# Bank_16_32_36.net
KiCad netlist of a schematic drawn in Altium Designer
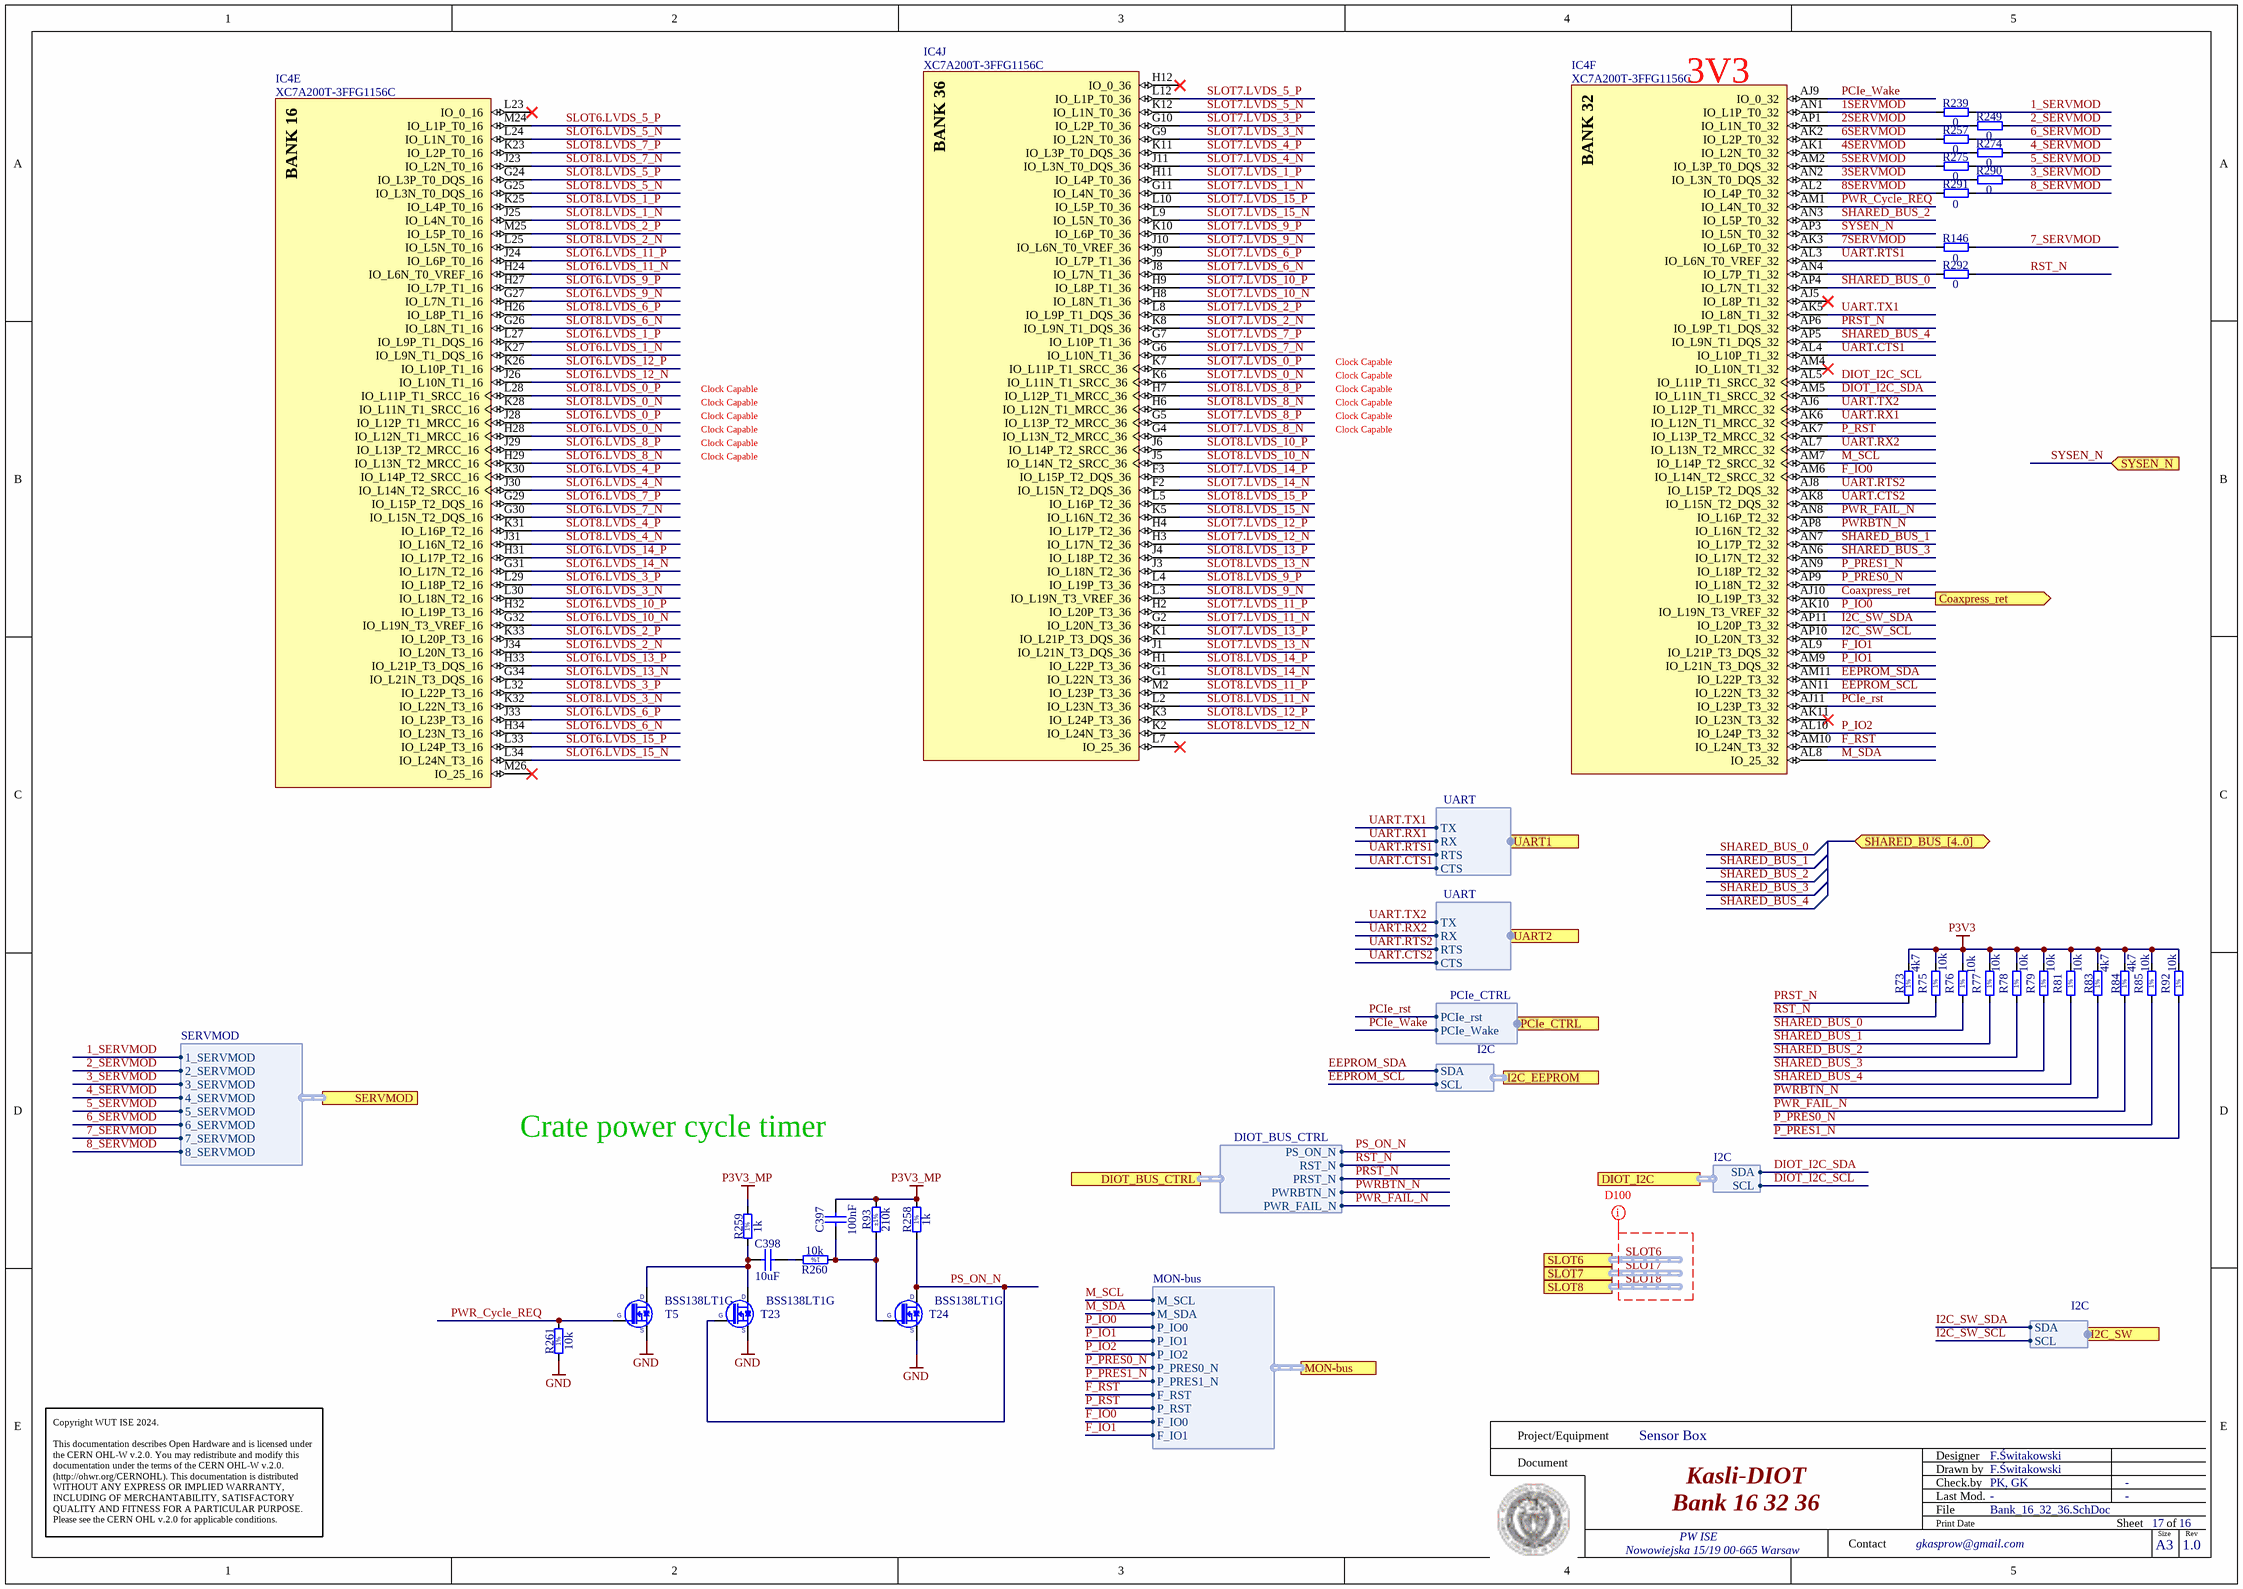
[diagram p0: Bank_16_32_36.SchDoc]

(export (version "E")
  (design (tool "Eeschema 10.0.6"))
  (components
    (comp (ref "C397")
      (value "100nF")
      (footprint "CAPC1005X55N")
      (description "Non-polarised capacitor")
      (fields
        (field (name "PART NUMBER") "CC0402_100NF_16V_10%_X7R")
        (field (name "VOLTAGE") "16V")
        (field (name "AUTHOR") "CERN DEM JLC")
      )
      (libsource (lib "Capacitors") (part "Capacitor - non polarized"))
    )
    (comp (ref "C398")
      (value "10uF")
      (footprint "CAPC3216X180N")
      (description "Non-polarised capacitor")
      (fields
        (field (name "PART NUMBER") "CC1206_10UF_25V_10%_X7R")
        (field (name "VOLTAGE") "25V")
        (field (name "AUTHOR") "CERN DEM JLC")
      )
      (libsource (lib "Capacitors") (part "Capacitor - non polarized"))
    )
    (comp (ref "IC4")
      (value "XC7A200T-3FFG1156C")
      (footprint "BGA1156C100P34X34_3500X3500X310")
      (description "Artix-7 FPGA, 500 User I/Os, 16 GTP, 1156-Ball BGA, , Speed Grade 3, Commercial Grade, Pb-Free")
      (fields (field (name "MANUFACTURER") "XILINX") (field (name "AUTHOR") "CERN DEM JLC"))
      (libsource (lib "ICs And Semiconductors") (part "XC7A200T-3FFG1156C"))
    )
    (comp (ref "R73")
      (value "4k7")
      (footprint "RESC1005X40N")
      (description "Resistor - 1%")
      (fields
        (field (name "PART NUMBER") "R0402_4K7_1%_0.0625W_100PPM")
        (field (name "POWER") "0.0625W")
        (field (name "AUTHOR") "CERN DEM JLC")
      )
      (libsource (lib "Resistors") (part "Resistor - 1%"))
    )
    (comp (ref "R75")
      (value "10k")
      (footprint "RESC1005X40N")
      (description "Resistor - 1%")
      (fields
        (field (name "PART NUMBER") "R0402_10K_1%_0.0625W_100PPM")
        (field (name "POWER") "0.0625W")
        (field (name "AUTHOR") "CERN DEM JLC")
      )
      (libsource (lib "Resistors") (part "Resistor - 1%"))
    )
    (comp (ref "R76")
      (value "10k")
      (footprint "RESC1005X40N")
      (description "Resistor - 1%")
      (fields
        (field (name "PART NUMBER") "R0402_10K_1%_0.0625W_100PPM")
        (field (name "POWER") "0.0625W")
        (field (name "AUTHOR") "CERN DEM JLC")
      )
      (libsource (lib "Resistors") (part "Resistor - 1%"))
    )
    (comp (ref "R77")
      (value "10k")
      (footprint "RESC1005X40N")
      (description "Resistor - 1%")
      (fields
        (field (name "PART NUMBER") "R0402_10K_1%_0.0625W_100PPM")
        (field (name "POWER") "0.0625W")
        (field (name "AUTHOR") "CERN DEM JLC")
      )
      (libsource (lib "Resistors") (part "Resistor - 1%"))
    )
    (comp (ref "R78")
      (value "10k")
      (footprint "RESC1005X40N")
      (description "Resistor - 1%")
      (fields
        (field (name "PART NUMBER") "R0402_10K_1%_0.0625W_100PPM")
        (field (name "POWER") "0.0625W")
        (field (name "AUTHOR") "CERN DEM JLC")
      )
      (libsource (lib "Resistors") (part "Resistor - 1%"))
    )
    (comp (ref "R79")
      (value "10k")
      (footprint "RESC1005X40N")
      (description "Resistor - 1%")
      (fields
        (field (name "PART NUMBER") "R0402_10K_1%_0.0625W_100PPM")
        (field (name "POWER") "0.0625W")
        (field (name "AUTHOR") "CERN DEM JLC")
      )
      (libsource (lib "Resistors") (part "Resistor - 1%"))
    )
    (comp (ref "R81")
      (value "10k")
      (footprint "RESC1005X40N")
      (description "Resistor - 1%")
      (fields
        (field (name "PART NUMBER") "R0402_10K_1%_0.0625W_100PPM")
        (field (name "POWER") "0.0625W")
        (field (name "AUTHOR") "CERN DEM JLC")
      )
      (libsource (lib "Resistors") (part "Resistor - 1%"))
    )
    (comp (ref "R83")
      (value "4k7")
      (footprint "RESC1005X40N")
      (description "Resistor - 1%")
      (fields
        (field (name "PART NUMBER") "R0402_4K7_1%_0.0625W_100PPM")
        (field (name "POWER") "0.0625W")
        (field (name "AUTHOR") "CERN DEM JLC")
      )
      (libsource (lib "Resistors") (part "Resistor - 1%"))
    )
    (comp (ref "R84")
      (value "4k7")
      (footprint "RESC1005X40N")
      (description "Resistor - 1%")
      (fields
        (field (name "PART NUMBER") "R0402_4K7_1%_0.0625W_100PPM")
        (field (name "POWER") "0.0625W")
        (field (name "AUTHOR") "CERN DEM JLC")
      )
      (libsource (lib "Resistors") (part "Resistor - 1%"))
    )
    (comp (ref "R85")
      (value "10k")
      (footprint "RESC1005X40N")
      (description "Resistor - 1%")
      (fields
        (field (name "PART NUMBER") "R0402_10K_1%_0.0625W_100PPM")
        (field (name "POWER") "0.0625W")
        (field (name "AUTHOR") "CERN DEM JLC")
      )
      (libsource (lib "Resistors") (part "Resistor - 1%"))
    )
    (comp (ref "R92")
      (value "10k")
      (footprint "RESC1005X40N")
      (description "Resistor - 1%")
      (fields
        (field (name "PART NUMBER") "R0402_10K_1%_0.0625W_100PPM")
        (field (name "POWER") "0.0625W")
        (field (name "AUTHOR") "CERN DEM JLC")
      )
      (libsource (lib "Resistors") (part "Resistor - 1%"))
    )
    (comp (ref "R93")
      (value "210k")
      (footprint "RESC1005X40N")
      (description "Resistor - 1%")
      (fields
        (field (name "TOLERANCE") "±1%")
        (field (name "PART NUMBER") "R0402_210K_1%_0.063W_100PPM")
        (field (name "POWER") "0.063W")
        (field (name "AUTHOR") "CERN DEM BC")
      )
      (libsource (lib "Resistors") (part "Resistor - 1%"))
    )
    (comp (ref "R146")
      (value "0")
      (footprint "RESC1005X40N")
      (description "Resistor")
      (fields
        (field (name "PART NUMBER") "R0402_0R_JUMPER")
        (field (name "MANUFACTURER") "GENERIC")
        (field (name "AUTHOR") "CERN DEM JLC")
      )
      (libsource (lib "Resistors") (part "Resistor"))
    )
    (comp (ref "R239")
      (value "0")
      (footprint "RESC1005X40N")
      (description "Resistor")
      (fields
        (field (name "PART NUMBER") "R0402_0R_JUMPER")
        (field (name "MANUFACTURER") "GENERIC")
        (field (name "AUTHOR") "CERN DEM JLC")
      )
      (libsource (lib "Resistors") (part "Resistor"))
    )
    (comp (ref "R249")
      (value "0")
      (footprint "RESC1005X40N")
      (description "Resistor")
      (fields
        (field (name "PART NUMBER") "R0402_0R_JUMPER")
        (field (name "MANUFACTURER") "GENERIC")
        (field (name "AUTHOR") "CERN DEM JLC")
      )
      (libsource (lib "Resistors") (part "Resistor"))
    )
    (comp (ref "R257")
      (value "0")
      (footprint "RESC1005X40N")
      (description "Resistor")
      (fields
        (field (name "PART NUMBER") "R0402_0R_JUMPER")
        (field (name "MANUFACTURER") "GENERIC")
        (field (name "AUTHOR") "CERN DEM JLC")
      )
      (libsource (lib "Resistors") (part "Resistor"))
    )
    (comp (ref "R258")
      (value "1k")
      (footprint "RESC1005X40N")
      (description "Resistor - 1%")
      (fields
        (field (name "PART NUMBER") "R0402_1K_1%_0.0625W_100PPM")
        (field (name "POWER") "0.0625W")
        (field (name "AUTHOR") "CERN DEM JLC")
      )
      (libsource (lib "Resistors") (part "Resistor - 1%"))
    )
    (comp (ref "R259")
      (value "1k")
      (footprint "RESC1005X40N")
      (description "Resistor - 1%")
      (fields
        (field (name "PART NUMBER") "R0402_1K_1%_0.0625W_100PPM")
        (field (name "POWER") "0.0625W")
        (field (name "AUTHOR") "CERN DEM JLC")
      )
      (libsource (lib "Resistors") (part "Resistor - 1%"))
    )
    (comp (ref "R260")
      (value "10k")
      (footprint "RESC1005X40N")
      (description "Resistor - 1%")
      (fields
        (field (name "PART NUMBER") "R0402_10K_1%_0.0625W_100PPM")
        (field (name "POWER") "0.0625W")
        (field (name "AUTHOR") "CERN DEM JLC")
      )
      (libsource (lib "Resistors") (part "Resistor - 1%"))
    )
    (comp (ref "R261")
      (value "10k")
      (footprint "RESC1005X40N")
      (description "Resistor - 1%")
      (fields
        (field (name "PART NUMBER") "R0402_10K_1%_0.0625W_100PPM")
        (field (name "POWER") "0.0625W")
        (field (name "AUTHOR") "CERN DEM JLC")
      )
      (libsource (lib "Resistors") (part "Resistor - 1%"))
    )
    (comp (ref "R274")
      (value "0")
      (footprint "RESC1005X40N")
      (description "Resistor")
      (fields
        (field (name "PART NUMBER") "R0402_0R_JUMPER")
        (field (name "MANUFACTURER") "GENERIC")
        (field (name "AUTHOR") "CERN DEM JLC")
      )
      (libsource (lib "Resistors") (part "Resistor"))
    )
    (comp (ref "R275")
      (value "0")
      (footprint "RESC1005X40N")
      (description "Resistor")
      (fields
        (field (name "PART NUMBER") "R0402_0R_JUMPER")
        (field (name "MANUFACTURER") "GENERIC")
        (field (name "AUTHOR") "CERN DEM JLC")
      )
      (libsource (lib "Resistors") (part "Resistor"))
    )
    (comp (ref "R290")
      (value "0")
      (footprint "RESC1005X40N")
      (description "Resistor")
      (fields
        (field (name "PART NUMBER") "R0402_0R_JUMPER")
        (field (name "MANUFACTURER") "GENERIC")
        (field (name "AUTHOR") "CERN DEM JLC")
      )
      (libsource (lib "Resistors") (part "Resistor"))
    )
    (comp (ref "R291")
      (value "0")
      (footprint "RESC1005X40N")
      (description "Resistor")
      (fields
        (field (name "PART NUMBER") "R0402_0R_JUMPER")
        (field (name "MANUFACTURER") "GENERIC")
        (field (name "AUTHOR") "CERN DEM JLC")
      )
      (libsource (lib "Resistors") (part "Resistor"))
    )
    (comp (ref "R292")
      (value "0")
      (footprint "RESC1005X40N")
      (description "Resistor")
      (fields
        (field (name "PART NUMBER") "R0402_0R_JUMPER")
        (field (name "MANUFACTURER") "GENERIC")
        (field (name "AUTHOR") "CERN DEM JLC")
      )
      (libsource (lib "Resistors") (part "Resistor"))
    )
    (comp (ref "T5")
      (value "BSS138LT1G")
      (footprint "SOT95P240X110-3N")
      (description "N-CHANNEL MOSFET WITH DIODE")
      (fields
        (field (name "MANUFACTURER") "ON SEMICONDUCTOR")
        (field (name "MANUFACTURER PART NUMBER") "BSS138L")
        (field (name "AUTHOR") "CERN DEM JLC")
      )
      (libsource (lib "ICs And Semiconductors") (part "N-MOSFET-D 1G 2S 3D"))
    )
    (comp (ref "T23")
      (value "BSS138LT1G")
      (footprint "SOT95P240X110-3N")
      (description "N-CHANNEL MOSFET WITH DIODE")
      (fields
        (field (name "MANUFACTURER") "ON SEMICONDUCTOR")
        (field (name "MANUFACTURER PART NUMBER") "BSS138L")
        (field (name "AUTHOR") "CERN DEM JLC")
      )
      (libsource (lib "ICs And Semiconductors") (part "N-MOSFET-D 1G 2S 3D"))
    )
    (comp (ref "T24")
      (value "BSS138LT1G")
      (footprint "SOT95P240X110-3N")
      (description "N-CHANNEL MOSFET WITH DIODE")
      (fields
        (field (name "MANUFACTURER") "ON SEMICONDUCTOR")
        (field (name "MANUFACTURER PART NUMBER") "BSS138L")
        (field (name "AUTHOR") "CERN DEM JLC")
      )
      (libsource (lib "ICs And Semiconductors") (part "N-MOSFET-D 1G 2S 3D"))
    )
  )
  (nets
    (net (code "10") (name "/1SERVMOD") (class "Default")
      (node (ref "IC4") (pin "AN1") (pinfunction "IO_L1P_T0_32_AN1") (pintype "bidirectional"))
      (node (ref "R239") (pin "1") (pinfunction "1_1") (pintype "passive"))
    )
    (net (code "11") (name "/1_SERVMOD") (class "Default")
      (node (ref "R239") (pin "2") (pinfunction "2_2") (pintype "passive"))
    )
    (net (code "12") (name "/2SERVMOD") (class "Default")
      (node (ref "IC4") (pin "AP1") (pinfunction "IO_L1N_T0_32_AP1") (pintype "bidirectional"))
      (node (ref "R249") (pin "1") (pinfunction "1_1") (pintype "passive"))
    )
    (net (code "13") (name "/2_SERVMOD") (class "Default")
      (node (ref "R249") (pin "2") (pinfunction "2_2") (pintype "passive"))
    )
    (net (code "14") (name "/3SERVMOD") (class "Default")
      (node (ref "IC4") (pin "AN2") (pinfunction "IO_L3N_T0_DQS_32_AN2") (pintype "bidirectional"))
      (node (ref "R290") (pin "1") (pinfunction "1_1") (pintype "passive"))
    )
    (net (code "15") (name "/3_SERVMOD") (class "Default")
      (node (ref "R290") (pin "2") (pinfunction "2_2") (pintype "passive"))
    )
    (net (code "16") (name "/4SERVMOD") (class "Default")
      (node (ref "IC4") (pin "AK1") (pinfunction "IO_L2N_T0_32_AK1") (pintype "bidirectional"))
      (node (ref "R274") (pin "1") (pinfunction "1_1") (pintype "passive"))
    )
    (net (code "17") (name "/4_SERVMOD") (class "Default")
      (node (ref "R274") (pin "2") (pinfunction "2_2") (pintype "passive"))
    )
    (net (code "18") (name "/5SERVMOD") (class "Default")
      (node (ref "IC4") (pin "AM2") (pinfunction "IO_L3P_T0_DQS_32_AM2") (pintype "bidirectional"))
      (node (ref "R275") (pin "1") (pinfunction "1_1") (pintype "passive"))
    )
    (net (code "19") (name "/5_SERVMOD") (class "Default")
      (node (ref "R275") (pin "2") (pinfunction "2_2") (pintype "passive"))
    )
    (net (code "20") (name "/6SERVMOD") (class "Default")
      (node (ref "IC4") (pin "AK2") (pinfunction "IO_L2P_T0_32_AK2") (pintype "bidirectional"))
      (node (ref "R257") (pin "1") (pinfunction "1_1") (pintype "passive"))
    )
    (net (code "21") (name "/6_SERVMOD") (class "Default")
      (node (ref "R257") (pin "2") (pinfunction "2_2") (pintype "passive"))
    )
    (net (code "22") (name "/7SERVMOD") (class "Default")
      (node (ref "IC4") (pin "AK3") (pinfunction "IO_L6P_T0_32_AK3") (pintype "bidirectional"))
      (node (ref "R146") (pin "1") (pinfunction "1_1") (pintype "passive"))
    )
    (net (code "23") (name "/7_SERVMOD") (class "Default")
      (node (ref "R146") (pin "2") (pinfunction "2_2") (pintype "passive"))
    )
    (net (code "24") (name "/8SERVMOD") (class "Default")
      (node (ref "IC4") (pin "AL2") (pinfunction "IO_L4P_T0_32_AL2") (pintype "bidirectional"))
      (node (ref "R291") (pin "1") (pinfunction "1_1") (pintype "passive"))
    )
    (net (code "25") (name "/8_SERVMOD") (class "Default")
      (node (ref "R291") (pin "2") (pinfunction "2_2") (pintype "passive"))
    )
    (net (code "26") (name "/Coaxpress_ret") (class "Default")
      (node (ref "IC4") (pin "AJ10") (pinfunction "IO_L19P_T3_32_AJ10") (pintype "bidirectional"))
    )
    (net (code "27") (name "/DIOT_I2C_SCL") (class "Default")
      (node (ref "IC4") (pin "AL5") (pinfunction "IO_L11P_T1_SRCC_32_AL5") (pintype "bidirectional"))
    )
    (net (code "28") (name "/DIOT_I2C_SDA") (class "Default")
      (node (ref "IC4") (pin "AM5") (pinfunction "IO_L11N_T1_SRCC_32_AM5") (pintype "bidirectional"))
    )
    (net (code "29") (name "/EEPROM_SCL") (class "Default")
      (node (ref "IC4") (pin "AN11") (pinfunction "IO_L22N_T3_32_AN11") (pintype "bidirectional"))
    )
    (net (code "30") (name "/EEPROM_SDA") (class "Default")
      (node (ref "IC4") (pin "AM11") (pinfunction "IO_L22P_T3_32_AM11") (pintype "bidirectional"))
    )
    (net (code "31") (name "/F_IO0") (class "Default")
      (node (ref "IC4") (pin "AM6") (pinfunction "IO_L14N_T2_SRCC_32_AM6") (pintype "bidirectional"))
    )
    (net (code "32") (name "/F_IO1") (class "Default")
      (node (ref "IC4") (pin "AL9") (pinfunction "IO_L21P_T3_DQS_32_AL9") (pintype "bidirectional"))
    )
    (net (code "33") (name "/F_RST") (class "Default")
      (node (ref "IC4") (pin "AM10") (pinfunction "IO_L24N_T3_32_AM10") (pintype "bidirectional"))
    )
    (net (code "34") (name "/I2C_SW_SCL") (class "Default")
      (node (ref "IC4") (pin "AP10") (pinfunction "IO_L20N_T3_32_AP10") (pintype "bidirectional"))
    )
    (net (code "35") (name "/I2C_SW_SDA") (class "Default")
      (node (ref "IC4") (pin "AP11") (pinfunction "IO_L20P_T3_32_AP11") (pintype "bidirectional"))
    )
    (net (code "36") (name "/M_SCL") (class "Default")
      (node (ref "IC4") (pin "AM7") (pinfunction "IO_L14P_T2_SRCC_32_AM7") (pintype "bidirectional"))
    )
    (net (code "37") (name "/M_SDA") (class "Default")
      (node (ref "IC4") (pin "AL8") (pinfunction "IO_25_32_AL8") (pintype "bidirectional"))
    )
    (net (code "38") (name "/PCIe_Wake") (class "Default")
      (node (ref "IC4") (pin "AJ9") (pinfunction "IO_0_32_AJ9") (pintype "bidirectional"))
    )
    (net (code "39") (name "/PCIe_rst") (class "Default")
      (node (ref "IC4") (pin "AJ11") (pinfunction "IO_L23P_T3_32_AJ11") (pintype "bidirectional"))
    )
    (net (code "40") (name "/PRST_N") (class "Default")
      (node (ref "IC4") (pin "AP6") (pinfunction "IO_L9P_T1_DQS_32_AP6") (pintype "bidirectional"))
      (node (ref "R73") (pin "1") (pinfunction "1_1") (pintype "passive"))
    )
    (net (code "41") (name "/PS_ON_N") (class "Default")
      (node (ref "R258") (pin "1") (pinfunction "1_1") (pintype "passive"))
      (node (ref "T23") (pin "1") (pinfunction "G_1") (pintype "passive"))
      (node (ref "T24") (pin "3") (pinfunction "D_3") (pintype "passive"))
    )
    (net (code "42") (name "/PWRBTN_N") (class "Default")
      (node (ref "IC4") (pin "AP8") (pinfunction "IO_L16N_T2_32_AP8") (pintype "bidirectional"))
      (node (ref "R83") (pin "1") (pinfunction "1_1") (pintype "passive"))
    )
    (net (code "43") (name "/PWR_Cycle_REQ") (class "Default")
      (node (ref "IC4") (pin "AM1") (pinfunction "IO_L4N_T0_32_AM1") (pintype "bidirectional"))
      (node (ref "R261") (pin "2") (pinfunction "2_2") (pintype "passive"))
      (node (ref "T5") (pin "1") (pinfunction "G_1") (pintype "passive"))
    )
    (net (code "44") (name "/PWR_FAIL_N") (class "Default")
      (node (ref "IC4") (pin "AN8") (pinfunction "IO_L16P_T2_32_AN8") (pintype "bidirectional"))
      (node (ref "R84") (pin "1") (pinfunction "1_1") (pintype "passive"))
    )
    (net (code "45") (name "/P_IO0") (class "Default")
      (node (ref "IC4") (pin "AK10") (pinfunction "IO_L19N_T3_VREF_32_AK10") (pintype "bidirectional"))
    )
    (net (code "46") (name "/P_IO1") (class "Default")
      (node (ref "IC4") (pin "AM9") (pinfunction "IO_L21N_T3_DQS_32_AM9") (pintype "bidirectional"))
    )
    (net (code "47") (name "/P_IO2") (class "Default")
      (node (ref "IC4") (pin "AL10") (pinfunction "IO_L24P_T3_32_AL10") (pintype "bidirectional"))
    )
    (net (code "48") (name "/P_PRES0_N") (class "Default")
      (node (ref "IC4") (pin "AP9") (pinfunction "IO_L18N_T2_32_AP9") (pintype "bidirectional"))
      (node (ref "R85") (pin "1") (pinfunction "1_1") (pintype "passive"))
    )
    (net (code "49") (name "/P_PRES1_N") (class "Default")
      (node (ref "IC4") (pin "AN9") (pinfunction "IO_L18P_T2_32_AN9") (pintype "bidirectional"))
      (node (ref "R92") (pin "1") (pinfunction "1_1") (pintype "passive"))
    )
    (net (code "50") (name "/P_RST") (class "Default")
      (node (ref "IC4") (pin "AK7") (pinfunction "IO_L13P_T2_MRCC_32_AK7") (pintype "bidirectional"))
    )
    (net (code "51") (name "/RST_N") (class "Default")
      (node (ref "R292") (pin "2") (pinfunction "2_2") (pintype "passive"))
      (node (ref "R75") (pin "1") (pinfunction "1_1") (pintype "passive"))
    )
    (net (code "52") (name "/SHARED_BUS_0") (class "Default")
      (node (ref "IC4") (pin "AP4") (pinfunction "IO_L7N_T1_32_AP4") (pintype "bidirectional"))
      (node (ref "R76") (pin "1") (pinfunction "1_1") (pintype "passive"))
    )
    (net (code "53") (name "/SHARED_BUS_1") (class "Default")
      (node (ref "IC4") (pin "AN7") (pinfunction "IO_L17P_T2_32_AN7") (pintype "bidirectional"))
      (node (ref "R77") (pin "1") (pinfunction "1_1") (pintype "passive"))
    )
    (net (code "54") (name "/SHARED_BUS_2") (class "Default")
      (node (ref "IC4") (pin "AN3") (pinfunction "IO_L5P_T0_32_AN3") (pintype "bidirectional"))
      (node (ref "R78") (pin "1") (pinfunction "1_1") (pintype "passive"))
    )
    (net (code "55") (name "/SHARED_BUS_3") (class "Default")
      (node (ref "IC4") (pin "AN6") (pinfunction "IO_L17N_T2_32_AN6") (pintype "bidirectional"))
      (node (ref "R79") (pin "1") (pinfunction "1_1") (pintype "passive"))
    )
    (net (code "56") (name "/SHARED_BUS_4") (class "Default")
      (node (ref "IC4") (pin "AP5") (pinfunction "IO_L9N_T1_DQS_32_AP5") (pintype "bidirectional"))
      (node (ref "R81") (pin "1") (pinfunction "1_1") (pintype "passive"))
    )
    (net (code "58") (name "/SLOT6.LVDS_0_N") (class "Default")
      (node (ref "IC4") (pin "H28") (pinfunction "IO_L12N_T1_MRCC_16_H28") (pintype "bidirectional"))
    )
    (net (code "59") (name "/SLOT6.LVDS_0_P") (class "Default")
      (node (ref "IC4") (pin "J28") (pinfunction "IO_L12P_T1_MRCC_16_J28") (pintype "bidirectional"))
    )
    (net (code "60") (name "/SLOT6.LVDS_1_N") (class "Default")
      (node (ref "IC4") (pin "K27") (pinfunction "IO_L9N_T1_DQS_16_K27") (pintype "bidirectional"))
    )
    (net (code "61") (name "/SLOT6.LVDS_1_P") (class "Default")
      (node (ref "IC4") (pin "L27") (pinfunction "IO_L9P_T1_DQS_16_L27") (pintype "bidirectional"))
    )
    (net (code "62") (name "/SLOT6.LVDS_2_N") (class "Default")
      (node (ref "IC4") (pin "J34") (pinfunction "IO_L20N_T3_16_J34") (pintype "bidirectional"))
    )
    (net (code "63") (name "/SLOT6.LVDS_2_P") (class "Default")
      (node (ref "IC4") (pin "K33") (pinfunction "IO_L20P_T3_16_K33") (pintype "bidirectional"))
    )
    (net (code "64") (name "/SLOT6.LVDS_3_N") (class "Default")
      (node (ref "IC4") (pin "L30") (pinfunction "IO_L18N_T2_16_L30") (pintype "bidirectional"))
    )
    (net (code "65") (name "/SLOT6.LVDS_3_P") (class "Default")
      (node (ref "IC4") (pin "L29") (pinfunction "IO_L18P_T2_16_L29") (pintype "bidirectional"))
    )
    (net (code "66") (name "/SLOT6.LVDS_4_N") (class "Default")
      (node (ref "IC4") (pin "J30") (pinfunction "IO_L14N_T2_SRCC_16_J30") (pintype "bidirectional"))
    )
    (net (code "67") (name "/SLOT6.LVDS_4_P") (class "Default")
      (node (ref "IC4") (pin "K30") (pinfunction "IO_L14P_T2_SRCC_16_K30") (pintype "bidirectional"))
    )
    (net (code "68") (name "/SLOT6.LVDS_5_N") (class "Default")
      (node (ref "IC4") (pin "L24") (pinfunction "IO_L1N_T0_16_L24") (pintype "bidirectional"))
    )
    (net (code "69") (name "/SLOT6.LVDS_5_P") (class "Default")
      (node (ref "IC4") (pin "M24") (pinfunction "IO_L1P_T0_16_M24") (pintype "bidirectional"))
    )
    (net (code "70") (name "/SLOT6.LVDS_6_N") (class "Default")
      (node (ref "IC4") (pin "H34") (pinfunction "IO_L23N_T3_16_H34") (pintype "bidirectional"))
    )
    (net (code "71") (name "/SLOT6.LVDS_6_P") (class "Default")
      (node (ref "IC4") (pin "J33") (pinfunction "IO_L23P_T3_16_J33") (pintype "bidirectional"))
    )
    (net (code "72") (name "/SLOT6.LVDS_7_N") (class "Default")
      (node (ref "IC4") (pin "G30") (pinfunction "IO_L15N_T2_DQS_16_G30") (pintype "bidirectional"))
    )
    (net (code "73") (name "/SLOT6.LVDS_7_P") (class "Default")
      (node (ref "IC4") (pin "G29") (pinfunction "IO_L15P_T2_DQS_16_G29") (pintype "bidirectional"))
    )
    (net (code "74") (name "/SLOT6.LVDS_8_N") (class "Default")
      (node (ref "IC4") (pin "H29") (pinfunction "IO_L13N_T2_MRCC_16_H29") (pintype "bidirectional"))
    )
    (net (code "75") (name "/SLOT6.LVDS_8_P") (class "Default")
      (node (ref "IC4") (pin "J29") (pinfunction "IO_L13P_T2_MRCC_16_J29") (pintype "bidirectional"))
    )
    (net (code "76") (name "/SLOT6.LVDS_9_N") (class "Default")
      (node (ref "IC4") (pin "G27") (pinfunction "IO_L7N_T1_16_G27") (pintype "bidirectional"))
    )
    (net (code "77") (name "/SLOT6.LVDS_9_P") (class "Default")
      (node (ref "IC4") (pin "H27") (pinfunction "IO_L7P_T1_16_H27") (pintype "bidirectional"))
    )
    (net (code "78") (name "/SLOT6.LVDS_10_N") (class "Default")
      (node (ref "IC4") (pin "G32") (pinfunction "IO_L19N_T3_VREF_16_G32") (pintype "bidirectional"))
    )
    (net (code "79") (name "/SLOT6.LVDS_10_P") (class "Default")
      (node (ref "IC4") (pin "H32") (pinfunction "IO_L19P_T3_16_H32") (pintype "bidirectional"))
    )
    (net (code "80") (name "/SLOT6.LVDS_11_N") (class "Default")
      (node (ref "IC4") (pin "H24") (pinfunction "IO_L6N_T0_VREF_16_H24") (pintype "bidirectional"))
    )
    (net (code "81") (name "/SLOT6.LVDS_11_P") (class "Default")
      (node (ref "IC4") (pin "J24") (pinfunction "IO_L6P_T0_16_J24") (pintype "bidirectional"))
    )
    (net (code "82") (name "/SLOT6.LVDS_12_N") (class "Default")
      (node (ref "IC4") (pin "J26") (pinfunction "IO_L10N_T1_16_J26") (pintype "bidirectional"))
    )
    (net (code "83") (name "/SLOT6.LVDS_12_P") (class "Default")
      (node (ref "IC4") (pin "K26") (pinfunction "IO_L10P_T1_16_K26") (pintype "bidirectional"))
    )
    (net (code "84") (name "/SLOT6.LVDS_13_N") (class "Default")
      (node (ref "IC4") (pin "G34") (pinfunction "IO_L21N_T3_DQS_16_G34") (pintype "bidirectional"))
    )
    (net (code "85") (name "/SLOT6.LVDS_13_P") (class "Default")
      (node (ref "IC4") (pin "H33") (pinfunction "IO_L21P_T3_DQS_16_H33") (pintype "bidirectional"))
    )
    (net (code "86") (name "/SLOT6.LVDS_14_N") (class "Default")
      (node (ref "IC4") (pin "G31") (pinfunction "IO_L17N_T2_16_G31") (pintype "bidirectional"))
    )
    (net (code "87") (name "/SLOT6.LVDS_14_P") (class "Default")
      (node (ref "IC4") (pin "H31") (pinfunction "IO_L17P_T2_16_H31") (pintype "bidirectional"))
    )
    (net (code "88") (name "/SLOT6.LVDS_15_N") (class "Default")
      (node (ref "IC4") (pin "L34") (pinfunction "IO_L24N_T3_16_L34") (pintype "bidirectional"))
    )
    (net (code "89") (name "/SLOT6.LVDS_15_P") (class "Default")
      (node (ref "IC4") (pin "L33") (pinfunction "IO_L24P_T3_16_L33") (pintype "bidirectional"))
    )
    (net (code "90") (name "/SLOT7.LVDS_0_N") (class "Default")
      (node (ref "IC4") (pin "K6") (pinfunction "IO_L11N_T1_SRCC_36_K6") (pintype "bidirectional"))
    )
    (net (code "91") (name "/SLOT7.LVDS_0_P") (class "Default")
      (node (ref "IC4") (pin "K7") (pinfunction "IO_L11P_T1_SRCC_36_K7") (pintype "bidirectional"))
    )
    (net (code "92") (name "/SLOT7.LVDS_1_N") (class "Default")
      (node (ref "IC4") (pin "G11") (pinfunction "IO_L4N_T0_36_G11") (pintype "bidirectional"))
    )
    (net (code "93") (name "/SLOT7.LVDS_1_P") (class "Default")
      (node (ref "IC4") (pin "H11") (pinfunction "IO_L4P_T0_36_H11") (pintype "bidirectional"))
    )
    (net (code "94") (name "/SLOT7.LVDS_2_N") (class "Default")
      (node (ref "IC4") (pin "K8") (pinfunction "IO_L9N_T1_DQS_36_K8") (pintype "bidirectional"))
    )
    (net (code "95") (name "/SLOT7.LVDS_2_P") (class "Default")
      (node (ref "IC4") (pin "L8") (pinfunction "IO_L9P_T1_DQS_36_L8") (pintype "bidirectional"))
    )
    (net (code "96") (name "/SLOT7.LVDS_3_N") (class "Default")
      (node (ref "IC4") (pin "G9") (pinfunction "IO_L2N_T0_36_G9") (pintype "bidirectional"))
    )
    (net (code "97") (name "/SLOT7.LVDS_3_P") (class "Default")
      (node (ref "IC4") (pin "G10") (pinfunction "IO_L2P_T0_36_G10") (pintype "bidirectional"))
    )
    (net (code "98") (name "/SLOT7.LVDS_4_N") (class "Default")
      (node (ref "IC4") (pin "J11") (pinfunction "IO_L3N_T0_DQS_36_J11") (pintype "bidirectional"))
    )
    (net (code "99") (name "/SLOT7.LVDS_4_P") (class "Default")
      (node (ref "IC4") (pin "K11") (pinfunction "IO_L3P_T0_DQS_36_K11") (pintype "bidirectional"))
    )
    (net (code "100") (name "/SLOT7.LVDS_5_N") (class "Default")
      (node (ref "IC4") (pin "K12") (pinfunction "IO_L1N_T0_36_K12") (pintype "bidirectional"))
    )
    (net (code "101") (name "/SLOT7.LVDS_5_P") (class "Default")
      (node (ref "IC4") (pin "L12") (pinfunction "IO_L1P_T0_36_L12") (pintype "bidirectional"))
    )
    (net (code "102") (name "/SLOT7.LVDS_6_N") (class "Default")
      (node (ref "IC4") (pin "J8") (pinfunction "IO_L7N_T1_36_J8") (pintype "bidirectional"))
    )
    (net (code "103") (name "/SLOT7.LVDS_6_P") (class "Default")
      (node (ref "IC4") (pin "J9") (pinfunction "IO_L7P_T1_36_J9") (pintype "bidirectional"))
    )
    (net (code "104") (name "/SLOT7.LVDS_7_N") (class "Default")
      (node (ref "IC4") (pin "G6") (pinfunction "IO_L10N_T1_36_G6") (pintype "bidirectional"))
    )
    (net (code "105") (name "/SLOT7.LVDS_7_P") (class "Default")
      (node (ref "IC4") (pin "G7") (pinfunction "IO_L10P_T1_36_G7") (pintype "bidirectional"))
    )
    (net (code "106") (name "/SLOT7.LVDS_8_N") (class "Default")
      (node (ref "IC4") (pin "G4") (pinfunction "IO_L13N_T2_MRCC_36_G4") (pintype "bidirectional"))
    )
    (net (code "107") (name "/SLOT7.LVDS_8_P") (class "Default")
      (node (ref "IC4") (pin "G5") (pinfunction "IO_L13P_T2_MRCC_36_G5") (pintype "bidirectional"))
    )
    (net (code "108") (name "/SLOT7.LVDS_9_N") (class "Default")
      (node (ref "IC4") (pin "J10") (pinfunction "IO_L6N_T0_VREF_36_J10") (pintype "bidirectional"))
    )
    (net (code "109") (name "/SLOT7.LVDS_9_P") (class "Default")
      (node (ref "IC4") (pin "K10") (pinfunction "IO_L6P_T0_36_K10") (pintype "bidirectional"))
    )
    (net (code "110") (name "/SLOT7.LVDS_10_N") (class "Default")
      (node (ref "IC4") (pin "H8") (pinfunction "IO_L8N_T1_36_H8") (pintype "bidirectional"))
    )
    (net (code "111") (name "/SLOT7.LVDS_10_P") (class "Default")
      (node (ref "IC4") (pin "H9") (pinfunction "IO_L8P_T1_36_H9") (pintype "bidirectional"))
    )
    (net (code "112") (name "/SLOT7.LVDS_11_N") (class "Default")
      (node (ref "IC4") (pin "G2") (pinfunction "IO_L20N_T3_36_G2") (pintype "bidirectional"))
    )
    (net (code "113") (name "/SLOT7.LVDS_11_P") (class "Default")
      (node (ref "IC4") (pin "H2") (pinfunction "IO_L20P_T3_36_H2") (pintype "bidirectional"))
    )
    (net (code "114") (name "/SLOT7.LVDS_12_N") (class "Default")
      (node (ref "IC4") (pin "H3") (pinfunction "IO_L17N_T2_36_H3") (pintype "bidirectional"))
    )
    (net (code "115") (name "/SLOT7.LVDS_12_P") (class "Default")
      (node (ref "IC4") (pin "H4") (pinfunction "IO_L17P_T2_36_H4") (pintype "bidirectional"))
    )
    (net (code "116") (name "/SLOT7.LVDS_13_N") (class "Default")
      (node (ref "IC4") (pin "J1") (pinfunction "IO_L21N_T3_DQS_36_J1") (pintype "bidirectional"))
    )
    (net (code "117") (name "/SLOT7.LVDS_13_P") (class "Default")
      (node (ref "IC4") (pin "K1") (pinfunction "IO_L21P_T3_DQS_36_K1") (pintype "bidirectional"))
    )
    (net (code "118") (name "/SLOT7.LVDS_14_N") (class "Default")
      (node (ref "IC4") (pin "F2") (pinfunction "IO_L15N_T2_DQS_36_F2") (pintype "bidirectional"))
    )
    (net (code "119") (name "/SLOT7.LVDS_14_P") (class "Default")
      (node (ref "IC4") (pin "F3") (pinfunction "IO_L15P_T2_DQS_36_F3") (pintype "bidirectional"))
    )
    (net (code "120") (name "/SLOT7.LVDS_15_N") (class "Default")
      (node (ref "IC4") (pin "L9") (pinfunction "IO_L5N_T0_36_L9") (pintype "bidirectional"))
    )
    (net (code "121") (name "/SLOT7.LVDS_15_P") (class "Default")
      (node (ref "IC4") (pin "L10") (pinfunction "IO_L5P_T0_36_L10") (pintype "bidirectional"))
    )
    (net (code "122") (name "/SLOT8.LVDS_0_N") (class "Default")
      (node (ref "IC4") (pin "K28") (pinfunction "IO_L11N_T1_SRCC_16_K28") (pintype "bidirectional"))
    )
    (net (code "123") (name "/SLOT8.LVDS_0_P") (class "Default")
      (node (ref "IC4") (pin "L28") (pinfunction "IO_L11P_T1_SRCC_16_L28") (pintype "bidirectional"))
    )
    (net (code "124") (name "/SLOT8.LVDS_1_N") (class "Default")
      (node (ref "IC4") (pin "J25") (pinfunction "IO_L4N_T0_16_J25") (pintype "bidirectional"))
    )
    (net (code "125") (name "/SLOT8.LVDS_1_P") (class "Default")
      (node (ref "IC4") (pin "K25") (pinfunction "IO_L4P_T0_16_K25") (pintype "bidirectional"))
    )
    (net (code "126") (name "/SLOT8.LVDS_2_N") (class "Default")
      (node (ref "IC4") (pin "L25") (pinfunction "IO_L5N_T0_16_L25") (pintype "bidirectional"))
    )
    (net (code "127") (name "/SLOT8.LVDS_2_P") (class "Default")
      (node (ref "IC4") (pin "M25") (pinfunction "IO_L5P_T0_16_M25") (pintype "bidirectional"))
    )
    (net (code "128") (name "/SLOT8.LVDS_3_N") (class "Default")
      (node (ref "IC4") (pin "K32") (pinfunction "IO_L22N_T3_16_K32") (pintype "bidirectional"))
    )
    (net (code "129") (name "/SLOT8.LVDS_3_P") (class "Default")
      (node (ref "IC4") (pin "L32") (pinfunction "IO_L22P_T3_16_L32") (pintype "bidirectional"))
    )
    (net (code "130") (name "/SLOT8.LVDS_4_N") (class "Default")
      (node (ref "IC4") (pin "J31") (pinfunction "IO_L16N_T2_16_J31") (pintype "bidirectional"))
    )
    (net (code "131") (name "/SLOT8.LVDS_4_P") (class "Default")
      (node (ref "IC4") (pin "K31") (pinfunction "IO_L16P_T2_16_K31") (pintype "bidirectional"))
    )
    (net (code "132") (name "/SLOT8.LVDS_5_N") (class "Default")
      (node (ref "IC4") (pin "G25") (pinfunction "IO_L3N_T0_DQS_16_G25") (pintype "bidirectional"))
    )
    (net (code "133") (name "/SLOT8.LVDS_5_P") (class "Default")
      (node (ref "IC4") (pin "G24") (pinfunction "IO_L3P_T0_DQS_16_G24") (pintype "bidirectional"))
    )
    (net (code "134") (name "/SLOT8.LVDS_6_N") (class "Default")
      (node (ref "IC4") (pin "G26") (pinfunction "IO_L8N_T1_16_G26") (pintype "bidirectional"))
    )
    (net (code "135") (name "/SLOT8.LVDS_6_P") (class "Default")
      (node (ref "IC4") (pin "H26") (pinfunction "IO_L8P_T1_16_H26") (pintype "bidirectional"))
    )
    (net (code "136") (name "/SLOT8.LVDS_7_N") (class "Default")
      (node (ref "IC4") (pin "J23") (pinfunction "IO_L2N_T0_16_J23") (pintype "bidirectional"))
    )
    (net (code "137") (name "/SLOT8.LVDS_7_P") (class "Default")
      (node (ref "IC4") (pin "K23") (pinfunction "IO_L2P_T0_16_K23") (pintype "bidirectional"))
    )
    (net (code "138") (name "/SLOT8.LVDS_8_N") (class "Default")
      (node (ref "IC4") (pin "H6") (pinfunction "IO_L12N_T1_MRCC_36_H6") (pintype "bidirectional"))
    )
    (net (code "139") (name "/SLOT8.LVDS_8_P") (class "Default")
      (node (ref "IC4") (pin "H7") (pinfunction "IO_L12P_T1_MRCC_36_H7") (pintype "bidirectional"))
    )
    (net (code "140") (name "/SLOT8.LVDS_9_N") (class "Default")
      (node (ref "IC4") (pin "L3") (pinfunction "IO_L19N_T3_VREF_36_L3") (pintype "bidirectional"))
    )
    (net (code "141") (name "/SLOT8.LVDS_9_P") (class "Default")
      (node (ref "IC4") (pin "L4") (pinfunction "IO_L19P_T3_36_L4") (pintype "bidirectional"))
    )
    (net (code "142") (name "/SLOT8.LVDS_10_N") (class "Default")
      (node (ref "IC4") (pin "J5") (pinfunction "IO_L14N_T2_SRCC_36_J5") (pintype "bidirectional"))
    )
    (net (code "143") (name "/SLOT8.LVDS_10_P") (class "Default")
      (node (ref "IC4") (pin "J6") (pinfunction "IO_L14P_T2_SRCC_36_J6") (pintype "bidirectional"))
    )
    (net (code "144") (name "/SLOT8.LVDS_11_N") (class "Default")
      (node (ref "IC4") (pin "L2") (pinfunction "IO_L23N_T3_36_L2") (pintype "bidirectional"))
    )
    (net (code "145") (name "/SLOT8.LVDS_11_P") (class "Default")
      (node (ref "IC4") (pin "M2") (pinfunction "IO_L23P_T3_36_M2") (pintype "bidirectional"))
    )
    (net (code "146") (name "/SLOT8.LVDS_12_N") (class "Default")
      (node (ref "IC4") (pin "K2") (pinfunction "IO_L24N_T3_36_K2") (pintype "bidirectional"))
    )
    (net (code "147") (name "/SLOT8.LVDS_12_P") (class "Default")
      (node (ref "IC4") (pin "K3") (pinfunction "IO_L24P_T3_36_K3") (pintype "bidirectional"))
    )
    (net (code "148") (name "/SLOT8.LVDS_13_N") (class "Default")
      (node (ref "IC4") (pin "J3") (pinfunction "IO_L18N_T2_36_J3") (pintype "bidirectional"))
    )
    (net (code "149") (name "/SLOT8.LVDS_13_P") (class "Default")
      (node (ref "IC4") (pin "J4") (pinfunction "IO_L18P_T2_36_J4") (pintype "bidirectional"))
    )
    (net (code "150") (name "/SLOT8.LVDS_14_N") (class "Default")
      (node (ref "IC4") (pin "G1") (pinfunction "IO_L22N_T3_36_G1") (pintype "bidirectional"))
    )
    (net (code "151") (name "/SLOT8.LVDS_14_P") (class "Default")
      (node (ref "IC4") (pin "H1") (pinfunction "IO_L22P_T3_36_H1") (pintype "bidirectional"))
    )
    (net (code "152") (name "/SLOT8.LVDS_15_N") (class "Default")
      (node (ref "IC4") (pin "K5") (pinfunction "IO_L16N_T2_36_K5") (pintype "bidirectional"))
    )
    (net (code "153") (name "/SLOT8.LVDS_15_P") (class "Default")
      (node (ref "IC4") (pin "L5") (pinfunction "IO_L16P_T2_36_L5") (pintype "bidirectional"))
    )
    (net (code "154") (name "/SYSEN_N") (class "Default")
      (node (ref "IC4") (pin "AP3") (pinfunction "IO_L5N_T0_32_AP3") (pintype "bidirectional"))
    )
    (net (code "155") (name "/UART.CTS1") (class "Default")
      (node (ref "IC4") (pin "AL4") (pinfunction "IO_L10P_T1_32_AL4") (pintype "bidirectional"))
    )
    (net (code "156") (name "/UART.CTS2") (class "Default")
      (node (ref "IC4") (pin "AK8") (pinfunction "IO_L15N_T2_DQS_32_AK8") (pintype "bidirectional"))
    )
    (net (code "157") (name "/UART.RTS1") (class "Default")
      (node (ref "IC4") (pin "AL3") (pinfunction "IO_L6N_T0_VREF_32_AL3") (pintype "bidirectional"))
    )
    (net (code "158") (name "/UART.RTS2") (class "Default")
      (node (ref "IC4") (pin "AJ8") (pinfunction "IO_L15P_T2_DQS_32_AJ8") (pintype "bidirectional"))
    )
    (net (code "159") (name "/UART.RX1") (class "Default")
      (node (ref "IC4") (pin "AK6") (pinfunction "IO_L12N_T1_MRCC_32_AK6") (pintype "bidirectional"))
    )
    (net (code "160") (name "/UART.RX2") (class "Default")
      (node (ref "IC4") (pin "AL7") (pinfunction "IO_L13N_T2_MRCC_32_AL7") (pintype "bidirectional"))
    )
    (net (code "161") (name "/UART.TX1") (class "Default")
      (node (ref "IC4") (pin "AK5") (pinfunction "IO_L8N_T1_32_AK5") (pintype "bidirectional"))
    )
    (net (code "162") (name "/UART.TX2") (class "Default")
      (node (ref "IC4") (pin "AJ6") (pinfunction "IO_L12P_T1_MRCC_32_AJ6") (pintype "bidirectional"))
    )
    (net (code "172") (name "GND") (class "Default")
      (node (ref "R261") (pin "1") (pinfunction "1_1") (pintype "passive"))
      (node (ref "T23") (pin "2") (pinfunction "S_2") (pintype "passive"))
      (node (ref "T24") (pin "2") (pinfunction "S_2") (pintype "passive"))
      (node (ref "T5") (pin "2") (pinfunction "S_2") (pintype "passive"))
    )
    (net (code "173") (name "Net-(C398-Pad2)") (class "Default")
      (node (ref "C398") (pin "2") (pinfunction "2_2") (pintype "passive"))
      (node (ref "R260") (pin "2") (pinfunction "2_2") (pintype "passive"))
    )
    (net (code "174") (name "Net-(IC4F-IO_L7P_T1_32)") (class "Default")
      (node (ref "IC4") (pin "AN4") (pinfunction "IO_L7P_T1_32_AN4") (pintype "bidirectional"))
      (node (ref "R292") (pin "1") (pinfunction "1_1") (pintype "passive"))
    )
    (net (code "175") (name "Net-(T23-D)") (class "Default")
      (node (ref "C398") (pin "1") (pinfunction "1_1") (pintype "passive"))
      (node (ref "R259") (pin "1") (pinfunction "1_1") (pintype "passive"))
      (node (ref "T23") (pin "3") (pinfunction "D_3") (pintype "passive"))
      (node (ref "T5") (pin "3") (pinfunction "D_3") (pintype "passive"))
    )
    (net (code "176") (name "Net-(T24-G)") (class "Default")
      (node (ref "C397") (pin "1") (pinfunction "1_1") (pintype "passive"))
      (node (ref "R260") (pin "1") (pinfunction "1_1") (pintype "passive"))
      (node (ref "R93") (pin "1") (pinfunction "1_1") (pintype "passive"))
      (node (ref "T24") (pin "1") (pinfunction "G_1") (pintype "passive"))
    )
    (net (code "177") (name "P3V3") (class "Default")
      (node (ref "R73") (pin "2") (pinfunction "2_2") (pintype "passive"))
      (node (ref "R75") (pin "2") (pinfunction "2_2") (pintype "passive"))
      (node (ref "R76") (pin "2") (pinfunction "2_2") (pintype "passive"))
      (node (ref "R77") (pin "2") (pinfunction "2_2") (pintype "passive"))
      (node (ref "R78") (pin "2") (pinfunction "2_2") (pintype "passive"))
      (node (ref "R79") (pin "2") (pinfunction "2_2") (pintype "passive"))
      (node (ref "R81") (pin "2") (pinfunction "2_2") (pintype "passive"))
      (node (ref "R83") (pin "2") (pinfunction "2_2") (pintype "passive"))
      (node (ref "R84") (pin "2") (pinfunction "2_2") (pintype "passive"))
      (node (ref "R85") (pin "2") (pinfunction "2_2") (pintype "passive"))
      (node (ref "R92") (pin "2") (pinfunction "2_2") (pintype "passive"))
    )
    (net (code "178") (name "P3V3_MP") (class "Default")
      (node (ref "C397") (pin "2") (pinfunction "2_2") (pintype "passive"))
      (node (ref "R258") (pin "2") (pinfunction "2_2") (pintype "passive"))
      (node (ref "R259") (pin "2") (pinfunction "2_2") (pintype "passive"))
      (node (ref "R93") (pin "2") (pinfunction "2_2") (pintype "passive"))
    )
    (net (code "179") (name "unconnected-(IC4E-IO_0_16-PadL23)") (class "Default")
      (node (ref "IC4") (pin "L23") (pinfunction "IO_0_16_L23") (pintype "bidirectional+no_connect"))
    )
    (net (code "180") (name "unconnected-(IC4E-IO_25_16-PadM26)") (class "Default")
      (node (ref "IC4") (pin "M26") (pinfunction "IO_25_16_M26") (pintype "bidirectional+no_connect"))
    )
    (net (code "181") (name "unconnected-(IC4F-IO_L8P_T1_32-PadAJ5)") (class "Default")
      (node (ref "IC4") (pin "AJ5") (pinfunction "IO_L8P_T1_32_AJ5") (pintype "bidirectional+no_connect"))
    )
    (net (code "182") (name "unconnected-(IC4F-IO_L10N_T1_32-PadAM4)") (class "Default")
      (node (ref "IC4") (pin "AM4") (pinfunction "IO_L10N_T1_32_AM4") (pintype "bidirectional+no_connect"))
    )
    (net (code "183") (name "unconnected-(IC4F-IO_L23N_T3_32-PadAK11)") (class "Default")
      (node (ref "IC4") (pin "AK11") (pinfunction "IO_L23N_T3_32_AK11") (pintype "bidirectional+no_connect"))
    )
    (net (code "184") (name "unconnected-(IC4J-IO_0_36-PadH12)") (class "Default")
      (node (ref "IC4") (pin "H12") (pinfunction "IO_0_36_H12") (pintype "bidirectional+no_connect"))
    )
    (net (code "185") (name "unconnected-(IC4J-IO_25_36-PadL7)") (class "Default")
      (node (ref "IC4") (pin "L7") (pinfunction "IO_25_36_L7") (pintype "bidirectional+no_connect"))
    )
  )
)
